# PSU.net
KiCad netlist of a schematic drawn in Altium Designer
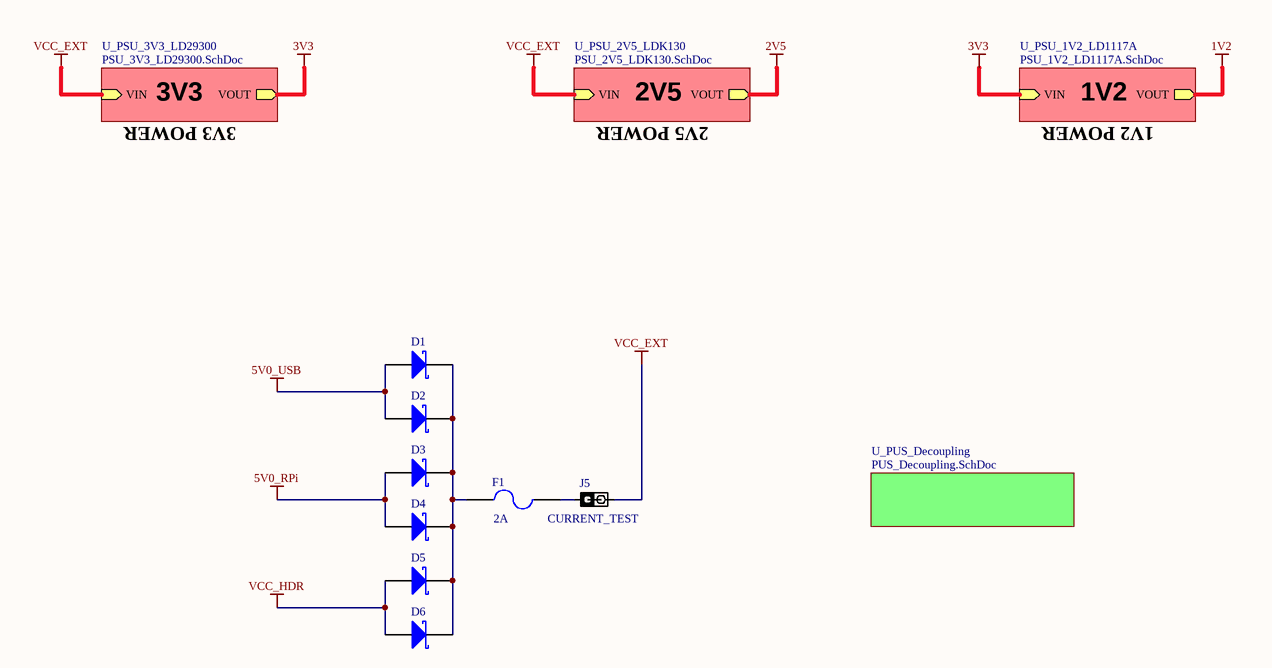
[diagram p0: PSU.SchDoc]

(export (version "E")
  (design (tool "Eeschema 10.0.6"))
  (components
    (comp (ref "D1")
      (value "D Schottky")
      (footprint "LED-0805-K")
      (description "Schottky Diode - SD0805S020S1R0")
      (fields (field (name "PUBLISHER") "Altium Limited"))
      (libsource (lib "Miscellaneous Devices") (part "D Schottky"))
    )
    (comp (ref "D2")
      (value "D Schottky")
      (footprint "LED-0805-K")
      (description "Schottky Diode - SD0805S020S1R0")
      (fields (field (name "PUBLISHER") "Altium Limited"))
      (libsource (lib "Miscellaneous Devices") (part "D Schottky"))
    )
    (comp (ref "D3")
      (value "D Schottky")
      (footprint "LED-0805-K")
      (description "Schottky Diode - SD0805S020S1R0")
      (fields (field (name "PUBLISHER") "Altium Limited"))
      (libsource (lib "Miscellaneous Devices") (part "D Schottky"))
    )
    (comp (ref "D4")
      (value "D Schottky")
      (footprint "LED-0805-K")
      (description "Schottky Diode - SD0805S020S1R0")
      (fields (field (name "PUBLISHER") "Altium Limited"))
      (libsource (lib "Miscellaneous Devices") (part "D Schottky"))
    )
    (comp (ref "D5")
      (value "D Schottky")
      (footprint "LED-0805-K")
      (description "Schottky Diode - SD0805S020S1R0")
      (fields (field (name "PUBLISHER") "Altium Limited"))
      (libsource (lib "Miscellaneous Devices") (part "D Schottky"))
    )
    (comp (ref "D6")
      (value "D Schottky")
      (footprint "LED-0805-K")
      (description "Schottky Diode - SD0805S020S1R0")
      (fields (field (name "PUBLISHER") "Altium Limited"))
      (libsource (lib "Miscellaneous Devices") (part "D Schottky"))
    )
    (comp (ref "F1")
      (value "Polyfuse_1812L200THPR")
      (footprint "1812")
      (description "Polyfuse")
      (fields (field (name "HOLD CURRENT") "2A") (field (name "PUBLISHER") "Altium Limited"))
      (libsource (lib "Miscellaneous Devices") (part "Fuse 2"))
    )
    (comp (ref "J5")
      (value "JMPR2")
      (footprint "JMPR2-CLOSED")
      (description "JMPR2 CLOSED BY DEFAULT")
      (fields
        (field (name "MANUFACTURER") "Sullins Connector Solutions")
        (field (name "MANUFACTURER PART NUMBER") "PBC36SAAN")
      )
      (libsource (lib "vh_altium_library") (part "JMPR2-CLOSED"))
    )
  )
  (nets
    (net (code "4") (name "5V0_RPi") (class "Default")
      (node (ref "D3") (pin "A") (pinfunction "A_A") (pintype "passive"))
      (node (ref "D4") (pin "A") (pinfunction "A_A") (pintype "passive"))
    )
    (net (code "5") (name "5V0_USB") (class "Default")
      (node (ref "D1") (pin "A") (pinfunction "A_A") (pintype "passive"))
      (node (ref "D2") (pin "A") (pinfunction "A_A") (pintype "passive"))
    )
    (net (code "6") (name "Net-(D1-PadK)") (class "Default")
      (node (ref "D1") (pin "K") (pinfunction "K_K") (pintype "passive"))
      (node (ref "D2") (pin "K") (pinfunction "K_K") (pintype "passive"))
      (node (ref "D3") (pin "K") (pinfunction "K_K") (pintype "passive"))
      (node (ref "D4") (pin "K") (pinfunction "K_K") (pintype "passive"))
      (node (ref "D5") (pin "K") (pinfunction "K_K") (pintype "passive"))
      (node (ref "D6") (pin "K") (pinfunction "K_K") (pintype "passive"))
      (node (ref "F1") (pin "1") (pinfunction "1_1") (pintype "passive"))
    )
    (net (code "7") (name "Net-(F1-Pad2)") (class "Default")
      (node (ref "F1") (pin "2") (pinfunction "2_2") (pintype "passive"))
      (node (ref "J5") (pin "1") (pintype "passive"))
    )
    (net (code "8") (name "VCC_EXT") (class "Default") (node (ref "J5") (pin "2") (pintype "passive")))
    (net (code "9") (name "VCC_HDR") (class "Default")
      (node (ref "D5") (pin "A") (pinfunction "A_A") (pintype "passive"))
      (node (ref "D6") (pin "A") (pinfunction "A_A") (pintype "passive"))
    )
  )
)
